# blink1mk3_004.net
KiCad netlist of a schematic drawn in EAGLE
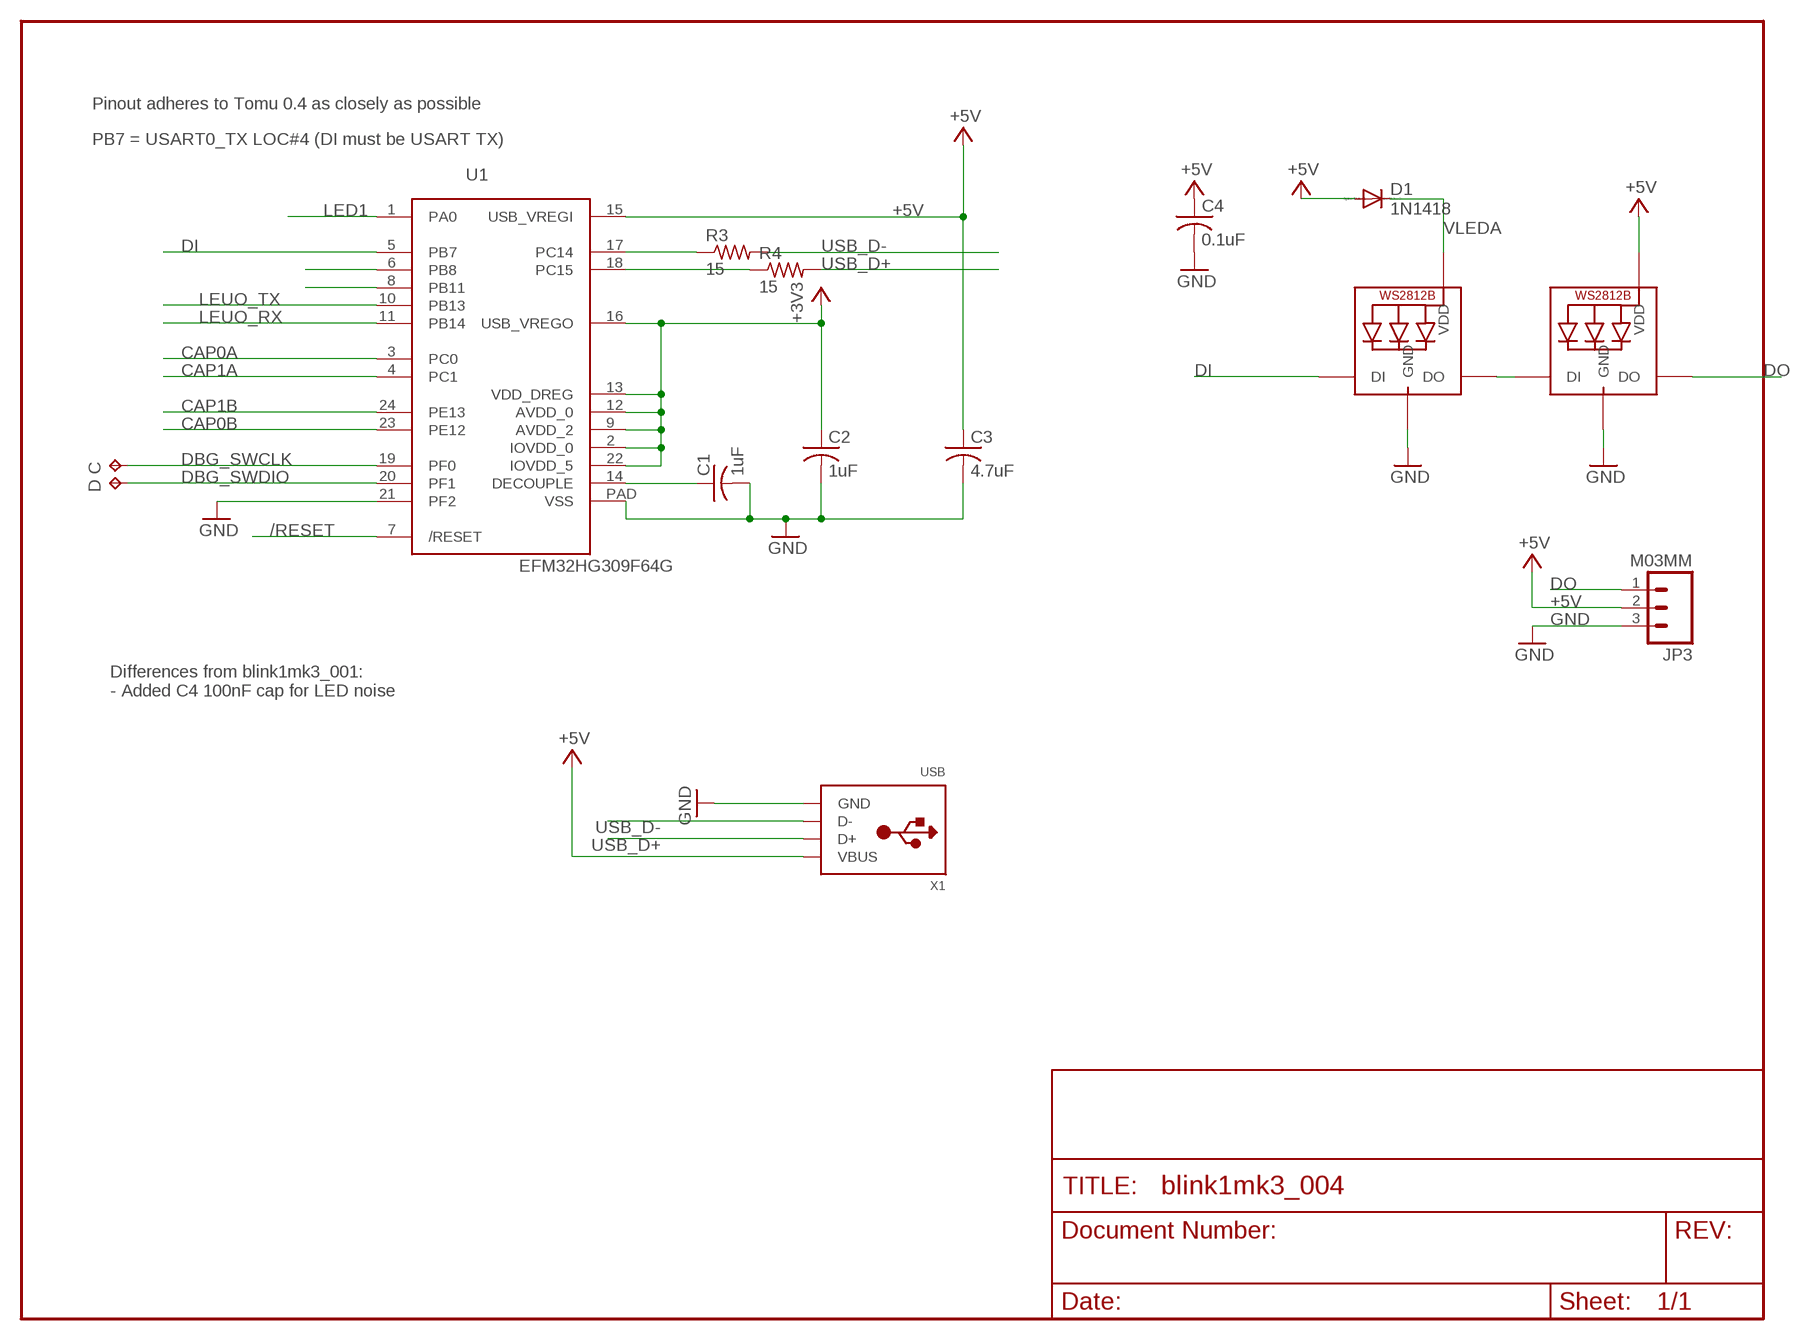
[diagram p0: schematic, sheet 1]

(export (version "E")
  (design (tool "Eeschema 10.0.6"))
  (components
    (comp (ref "C")
      (value "TPTP10R")
      (footprint "eagle-import:TP10R")
      (libsource (lib "eagle-import") (part "TPTP10R"))
    )
    (comp (ref "C1")
      (value "1uF")
      (footprint "eagle-import:C0402")
      (libsource (lib "eagle-import") (part "C-USC0402"))
    )
    (comp (ref "C2")
      (value "1uF")
      (footprint "eagle-import:C0402")
      (libsource (lib "eagle-import") (part "C-USC0402"))
    )
    (comp (ref "C3")
      (value "4.7uF")
      (footprint "eagle-import:C0402")
      (libsource (lib "eagle-import") (part "C-USC0402"))
    )
    (comp (ref "C4")
      (value "0.1uF")
      (footprint "eagle-import:C0402")
      (libsource (lib "eagle-import") (part "C-USC0402"))
    )
    (comp (ref "D")
      (value "TPTP10R")
      (footprint "eagle-import:TP10R")
      (libsource (lib "eagle-import") (part "TPTP10R"))
    )
    (comp (ref "D1")
      (value "1N1418")
      (footprint "eagle-import:SOD523")
      (libsource (lib "eagle-import") (part "DIODE-SOD523"))
    )
    (comp (ref "JP3")
      (value "M03MM")
      (footprint "eagle-import:1X03-1.5MM")
      (libsource (lib "eagle-import") (part "M03MM"))
    )
    (comp (ref "LED1")
      (value "WS2812B3535")
      (footprint "eagle-import:LED3535")
      (libsource (lib "eagle-import") (part "WS2812B3535"))
    )
    (comp (ref "LED2")
      (value "WS2812B3535")
      (footprint "eagle-import:LED3535")
      (libsource (lib "eagle-import") (part "WS2812B3535"))
    )
    (comp (ref "R3")
      (value "15")
      (footprint "eagle-import:R0402")
      (libsource (lib "eagle-import") (part "R-US_R0402"))
    )
    (comp (ref "R4")
      (value "15")
      (footprint "eagle-import:R0402")
      (libsource (lib "eagle-import") (part "R-US_R0402"))
    )
    (comp (ref "U1")
      (value "EFM32HG309F64G")
      (footprint "eagle-import:QFN24PAD")
      (libsource (lib "eagle-import") (part "EFM32HG309F64G"))
    )
    (comp (ref "X1")
      (value "USB")
      (footprint "eagle-import:MOLEX-48037-1000")
      (libsource (lib "eagle-import") (part "USB"))
    )
  )
  (nets
    (net (code "1") (name "+3V3") (class "Default")
      (node (ref "C2") (pin "1") (pinfunction "1_1") (pintype "passive"))
      (node (ref "U1") (pin "12") (pinfunction "AVDD_0_12") (pintype "bidirectional"))
      (node (ref "U1") (pin "13") (pinfunction "VDD_DREG_13") (pintype "bidirectional"))
      (node (ref "U1") (pin "16") (pinfunction "USB_VREGO_16") (pintype "bidirectional"))
      (node (ref "U1") (pin "2") (pinfunction "IOVDD_0_2") (pintype "bidirectional"))
      (node (ref "U1") (pin "22") (pinfunction "IOVDD_5_22") (pintype "bidirectional"))
      (node (ref "U1") (pin "9") (pinfunction "AVDD_2_9") (pintype "bidirectional"))
    )
    (net (code "2") (name "+5V") (class "Default")
      (node (ref "C3") (pin "1") (pinfunction "1_1") (pintype "passive"))
      (node (ref "C4") (pin "1") (pinfunction "1_1") (pintype "passive"))
      (node (ref "D1") (pin "A") (pinfunction "A_A") (pintype "passive"))
      (node (ref "JP3") (pin "2") (pinfunction "2_2") (pintype "passive"))
      (node (ref "LED2") (pin "2") (pinfunction "VDD_2") (pintype "power_in"))
      (node (ref "U1") (pin "15") (pinfunction "USB_VREGI_15") (pintype "bidirectional"))
      (node (ref "X1") (pin "1") (pinfunction "VBUS_1") (pintype "power_in"))
    )
    (net (code "3") (name "/CAP0A") (class "Default")
      (node (ref "U1") (pin "3") (pinfunction "PC0_3") (pintype "bidirectional"))
    )
    (net (code "4") (name "/CAP0B") (class "Default")
      (node (ref "U1") (pin "23") (pinfunction "PE12_23") (pintype "bidirectional"))
    )
    (net (code "5") (name "/CAP1A") (class "Default")
      (node (ref "U1") (pin "4") (pinfunction "PC1_4") (pintype "bidirectional"))
    )
    (net (code "6") (name "/CAP1B") (class "Default")
      (node (ref "U1") (pin "24") (pinfunction "PE13_24") (pintype "bidirectional"))
    )
    (net (code "7") (name "/DBG_SWCLK") (class "Default")
      (node (ref "C") (pin "TP") (pinfunction "TP_TP") (pintype "input"))
      (node (ref "U1") (pin "19") (pinfunction "PF0_19") (pintype "bidirectional"))
    )
    (net (code "8") (name "/DBG_SWDIO") (class "Default")
      (node (ref "D") (pin "TP") (pinfunction "TP_TP") (pintype "input"))
      (node (ref "U1") (pin "20") (pinfunction "PF1_20") (pintype "bidirectional"))
    )
    (net (code "9") (name "/DI") (class "Default")
      (node (ref "LED1") (pin "1") (pinfunction "DI_1") (pintype "input"))
      (node (ref "U1") (pin "5") (pinfunction "PB7_5") (pintype "bidirectional"))
    )
    (net (code "10") (name "/DO") (class "Default")
      (node (ref "JP3") (pin "1") (pinfunction "1_1") (pintype "passive"))
      (node (ref "LED2") (pin "3") (pinfunction "DO_3") (pintype "output"))
    )
    (net (code "11") (name "/LED1") (class "Default")
      (node (ref "U1") (pin "1") (pinfunction "PA0_1") (pintype "bidirectional"))
    )
    (net (code "12") (name "/LEUO_RX") (class "Default")
      (node (ref "U1") (pin "11") (pinfunction "PB14_11") (pintype "bidirectional"))
    )
    (net (code "13") (name "/LEUO_TX") (class "Default")
      (node (ref "U1") (pin "10") (pinfunction "PB13_10") (pintype "bidirectional"))
    )
    (net (code "14") (name "/USB_D+") (class "Default")
      (node (ref "R4") (pin "2") (pinfunction "2_2") (pintype "passive"))
      (node (ref "X1") (pin "3") (pinfunction "D+_3") (pintype "bidirectional"))
    )
    (net (code "15") (name "/USB_D-") (class "Default")
      (node (ref "R3") (pin "2") (pinfunction "2_2") (pintype "passive"))
      (node (ref "X1") (pin "2") (pinfunction "D-_2") (pintype "bidirectional"))
    )
    (net (code "16") (name "/VLEDA") (class "Default")
      (node (ref "D1") (pin "C") (pinfunction "C_C") (pintype "passive"))
      (node (ref "LED1") (pin "2") (pinfunction "VDD_2") (pintype "power_in"))
    )
    (net (code "17") (name "/{slash}RESET") (class "Default")
      (node (ref "U1") (pin "7") (pinfunction "/RESET_7") (pintype "bidirectional"))
    )
    (net (code "18") (name "GND") (class "Default")
      (node (ref "C1") (pin "2") (pinfunction "2_2") (pintype "passive"))
      (node (ref "C2") (pin "2") (pinfunction "2_2") (pintype "passive"))
      (node (ref "C3") (pin "2") (pinfunction "2_2") (pintype "passive"))
      (node (ref "C4") (pin "2") (pinfunction "2_2") (pintype "passive"))
      (node (ref "JP3") (pin "3") (pinfunction "3_3") (pintype "passive"))
      (node (ref "LED1") (pin "4") (pinfunction "GND_4") (pintype "power_in"))
      (node (ref "LED2") (pin "4") (pinfunction "GND_4") (pintype "power_in"))
      (node (ref "U1") (pin "21") (pinfunction "PF2_21") (pintype "bidirectional"))
      (node (ref "U1") (pin "PAD") (pinfunction "VSS_PAD") (pintype "bidirectional"))
      (node (ref "X1") (pin "4") (pinfunction "GND_4") (pintype "power_in"))
    )
    (net (code "19") (name "Net-(LED1-DO)") (class "Default")
      (node (ref "LED1") (pin "3") (pinfunction "DO_3") (pintype "output"))
      (node (ref "LED2") (pin "1") (pinfunction "DI_1") (pintype "input"))
    )
    (net (code "20") (name "Net-(U1-DECOUPLE)") (class "Default")
      (node (ref "C1") (pin "1") (pinfunction "1_1") (pintype "passive"))
      (node (ref "U1") (pin "14") (pinfunction "DECOUPLE_14") (pintype "bidirectional"))
    )
    (net (code "21") (name "Net-(U1-PC14)") (class "Default")
      (node (ref "R3") (pin "1") (pinfunction "1_1") (pintype "passive"))
      (node (ref "U1") (pin "17") (pinfunction "PC14_17") (pintype "bidirectional"))
    )
    (net (code "22") (name "Net-(U1-PC15)") (class "Default")
      (node (ref "R4") (pin "1") (pinfunction "1_1") (pintype "passive"))
      (node (ref "U1") (pin "18") (pinfunction "PC15_18") (pintype "bidirectional"))
    )
    (net (code "23") (name "unconnected-(U1-PB8-Pad6)") (class "Default")
      (node (ref "U1") (pin "6") (pinfunction "PB8_6") (pintype "bidirectional"))
    )
    (net (code "24") (name "unconnected-(U1-PB11-Pad8)") (class "Default")
      (node (ref "U1") (pin "8") (pinfunction "PB11_8") (pintype "bidirectional"))
    )
  )
)
